# TWE-Lite_USB.net
KiCad netlist of a schematic drawn in EAGLE
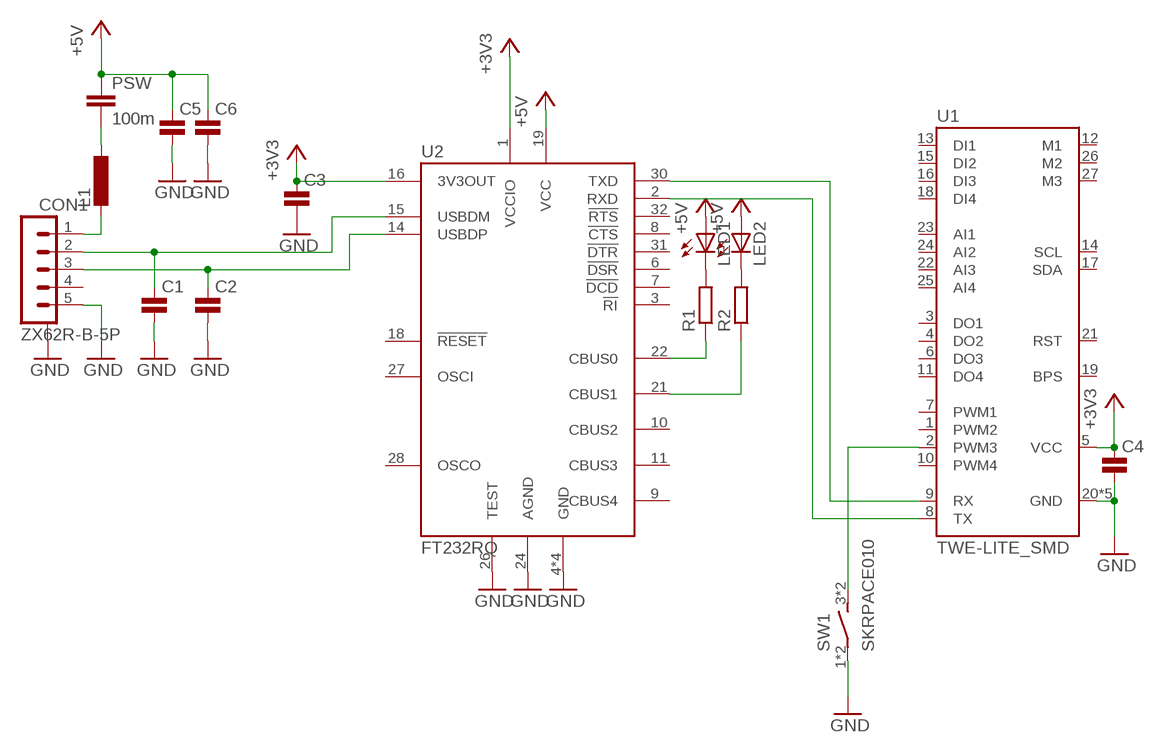
[diagram p0: schematic, sheet 1]

(export (version "E")
  (design (tool "Eeschema 10.0.6"))
  (components
    (comp (ref "C1")
      (value "C0402")
      (footprint "eagle-import:0402")
      (libsource (lib "eagle-import") (part "C0402"))
    )
    (comp (ref "C2")
      (value "C0402")
      (footprint "eagle-import:0402")
      (libsource (lib "eagle-import") (part "C0402"))
    )
    (comp (ref "C3")
      (value "C0402")
      (footprint "eagle-import:0402")
      (libsource (lib "eagle-import") (part "C0402"))
    )
    (comp (ref "C4")
      (value "C0402")
      (footprint "eagle-import:0402")
      (libsource (lib "eagle-import") (part "C0402"))
    )
    (comp (ref "C5")
      (value "C0402")
      (footprint "eagle-import:0402")
      (libsource (lib "eagle-import") (part "C0402"))
    )
    (comp (ref "C6")
      (value "C0402")
      (footprint "eagle-import:0402")
      (libsource (lib "eagle-import") (part "C0402"))
    )
    (comp (ref "CON1")
      (value "ZX62R-B-5P")
      (footprint "eagle-import:MICRO-B")
      (libsource (lib "eagle-import") (part "ZX62R-B-5P"))
    )
    (comp (ref "L1")
      (value "L-EU")
      (footprint "eagle-import:C0603K")
      (libsource (lib "eagle-import") (part "L-EU"))
    )
    (comp (ref "LED1")
      (value "LEDSML0603")
      (footprint "eagle-import:SML0603")
      (libsource (lib "eagle-import") (part "LEDSML0603"))
    )
    (comp (ref "LED2")
      (value "LEDSML0603")
      (footprint "eagle-import:SML0603")
      (libsource (lib "eagle-import") (part "LEDSML0603"))
    )
    (comp (ref "PSW")
      (value "100m")
      (footprint "eagle-import:C3225")
      (libsource (lib "eagle-import") (part "C-EUC3225"))
    )
    (comp (ref "R1")
      (value "R-EU_R0402")
      (footprint "eagle-import:R0402")
      (libsource (lib "eagle-import") (part "R-EU_R0402"))
    )
    (comp (ref "R2")
      (value "R-EU_R0402")
      (footprint "eagle-import:R0402")
      (libsource (lib "eagle-import") (part "R-EU_R0402"))
    )
    (comp (ref "SW1")
      (value "SKRPACE010")
      (footprint "eagle-import:SKRPACE010")
      (libsource (lib "eagle-import") (part "SKRPACE010"))
    )
    (comp (ref "U1")
      (value "TWE-LITE_SMD")
      (footprint "eagle-import:LITE")
      (libsource (lib "eagle-import") (part "TWE-LITE_SMD"))
    )
    (comp (ref "U2")
      (value "FT232RQ")
      (footprint "eagle-import:QFN32")
      (libsource (lib "eagle-import") (part "FT232RQ"))
    )
  )
  (nets
    (net (code "1") (name "+3V3") (class "Default")
      (node (ref "C3") (pin "1") (pinfunction "P$1_1") (pintype "passive"))
      (node (ref "C4") (pin "1") (pinfunction "P$1_1") (pintype "passive"))
      (node (ref "U1") (pin "5") (pinfunction "VCC_5") (pintype "power_in"))
      (node (ref "U2") (pin "1") (pinfunction "VCCIO_1") (pintype "power_in"))
      (node (ref "U2") (pin "16") (pinfunction "3V3OUT_16") (pintype "output"))
    )
    (net (code "2") (name "+5V") (class "Default")
      (node (ref "C5") (pin "1") (pinfunction "P$1_1") (pintype "passive"))
      (node (ref "C6") (pin "1") (pinfunction "P$1_1") (pintype "passive"))
      (node (ref "LED1") (pin "A") (pinfunction "A_A") (pintype "passive"))
      (node (ref "LED2") (pin "A") (pinfunction "A_A") (pintype "passive"))
      (node (ref "PSW") (pin "1") (pinfunction "1_1") (pintype "passive"))
      (node (ref "U2") (pin "19") (pinfunction "VCC_19") (pintype "power_in"))
    )
    (net (code "3") (name "GND") (class "Default")
      (node (ref "C1") (pin "2") (pinfunction "P$2_2") (pintype "passive"))
      (node (ref "C2") (pin "2") (pinfunction "P$2_2") (pintype "passive"))
      (node (ref "C3") (pin "2") (pinfunction "P$2_2") (pintype "passive"))
      (node (ref "C4") (pin "2") (pinfunction "P$2_2") (pintype "passive"))
      (node (ref "C5") (pin "2") (pinfunction "P$2_2") (pintype "passive"))
      (node (ref "C6") (pin "2") (pinfunction "P$2_2") (pintype "passive"))
      (node (ref "CON1") (pin "5") (pinfunction "1.VBUS_5") (pintype "passive"))
      (node (ref "CON1") (pin "CASE@1") (pinfunction "P$1_CASE@1") (pintype "bidirectional"))
      (node (ref "CON1") (pin "CASE@2") (pinfunction "P$1_CASE@2") (pintype "bidirectional"))
      (node (ref "CON1") (pin "CASE@3") (pinfunction "P$1_CASE@3") (pintype "bidirectional"))
      (node (ref "CON1") (pin "CASE@4") (pinfunction "P$1_CASE@4") (pintype "bidirectional"))
      (node (ref "SW1") (pin "1") (pinfunction "P_1") (pintype "passive"))
      (node (ref "SW1") (pin "2") (pinfunction "P_2") (pintype "passive"))
      (node (ref "U1") (pin "20") (pinfunction "GND_20") (pintype "power_in"))
      (node (ref "U1") (pin "28") (pinfunction "GND_28") (pintype "power_in"))
      (node (ref "U1") (pin "30") (pinfunction "GND_30") (pintype "power_in"))
      (node (ref "U1") (pin "31") (pinfunction "GND_31") (pintype "power_in"))
      (node (ref "U1") (pin "32") (pinfunction "GND_32") (pintype "power_in"))
      (node (ref "U2") (pin "17") (pinfunction "GND_17") (pintype "power_in"))
      (node (ref "U2") (pin "20") (pinfunction "GND_20") (pintype "power_in"))
      (node (ref "U2") (pin "24") (pinfunction "AGND_24") (pintype "power_in"))
      (node (ref "U2") (pin "26") (pinfunction "TEST_26") (pintype "input"))
      (node (ref "U2") (pin "4") (pinfunction "GND_4") (pintype "power_in"))
      (node (ref "U2") (pin "PAD") (pinfunction "GND_PAD") (pintype "power_in"))
    )
    (net (code "4") (name "Net-(C1-P$1)") (class "Default")
      (node (ref "C1") (pin "1") (pinfunction "P$1_1") (pintype "passive"))
      (node (ref "CON1") (pin "2") (pinfunction "4.ID_2") (pintype "passive"))
      (node (ref "U2") (pin "15") (pinfunction "USBDM_15") (pintype "bidirectional"))
    )
    (net (code "5") (name "Net-(C2-P$1)") (class "Default")
      (node (ref "C2") (pin "1") (pinfunction "P$1_1") (pintype "passive"))
      (node (ref "CON1") (pin "3") (pinfunction "3.D+_3") (pintype "passive"))
      (node (ref "U2") (pin "14") (pinfunction "USBDP_14") (pintype "bidirectional"))
    )
    (net (code "6") (name "Net-(CON1-5.GND)") (class "Default")
      (node (ref "CON1") (pin "1") (pinfunction "5.GND_1") (pintype "passive"))
      (node (ref "L1") (pin "2") (pinfunction "2_2") (pintype "passive"))
    )
    (net (code "7") (name "Net-(L1-Pad1)") (class "Default")
      (node (ref "L1") (pin "1") (pinfunction "1_1") (pintype "passive"))
      (node (ref "PSW") (pin "2") (pinfunction "2_2") (pintype "passive"))
    )
    (net (code "8") (name "Net-(LED1-PadC)") (class "Default")
      (node (ref "LED1") (pin "C") (pinfunction "C_C") (pintype "passive"))
      (node (ref "R1") (pin "2") (pinfunction "2_2") (pintype "passive"))
    )
    (net (code "9") (name "Net-(LED2-PadC)") (class "Default")
      (node (ref "LED2") (pin "C") (pinfunction "C_C") (pintype "passive"))
      (node (ref "R2") (pin "2") (pinfunction "2_2") (pintype "passive"))
    )
    (net (code "10") (name "Net-(U1-PWM3)") (class "Default")
      (node (ref "SW1") (pin "3") (pinfunction "S_3") (pintype "passive"))
      (node (ref "SW1") (pin "4") (pinfunction "S_4") (pintype "passive"))
      (node (ref "U1") (pin "2") (pinfunction "PWM3_2") (pintype "output"))
    )
    (net (code "11") (name "Net-(U1-RX)") (class "Default")
      (node (ref "U1") (pin "9") (pinfunction "RX_9") (pintype "input"))
      (node (ref "U2") (pin "30") (pinfunction "TXD_30") (pintype "output"))
    )
    (net (code "12") (name "Net-(U1-TX)") (class "Default")
      (node (ref "U1") (pin "8") (pinfunction "TX_8") (pintype "output"))
      (node (ref "U2") (pin "2") (pinfunction "RXD_2") (pintype "input"))
    )
    (net (code "13") (name "Net-(U2-CBUS0)") (class "Default")
      (node (ref "R1") (pin "1") (pinfunction "1_1") (pintype "passive"))
      (node (ref "U2") (pin "22") (pinfunction "CBUS0_22") (pintype "bidirectional"))
    )
    (net (code "14") (name "Net-(U2-CBUS1)") (class "Default")
      (node (ref "R2") (pin "1") (pinfunction "1_1") (pintype "passive"))
      (node (ref "U2") (pin "21") (pinfunction "CBUS1_21") (pintype "bidirectional"))
    )
    (net (code "15") (name "unconnected-(CON1-2.D--Pad4)") (class "Default")
      (node (ref "CON1") (pin "4") (pinfunction "2.D-_4") (pintype "passive"))
    )
    (net (code "16") (name "unconnected-(U1-AI1-Pad23)") (class "Default")
      (node (ref "U1") (pin "23") (pinfunction "AI1_23") (pintype "input"))
    )
    (net (code "17") (name "unconnected-(U1-AI2-Pad24)") (class "Default")
      (node (ref "U1") (pin "24") (pinfunction "AI2_24") (pintype "input"))
    )
    (net (code "18") (name "unconnected-(U1-AI3-Pad22)") (class "Default")
      (node (ref "U1") (pin "22") (pinfunction "AI3_22") (pintype "input"))
    )
    (net (code "19") (name "unconnected-(U1-AI4-Pad25)") (class "Default")
      (node (ref "U1") (pin "25") (pinfunction "AI4_25") (pintype "input"))
    )
    (net (code "20") (name "unconnected-(U1-BPS-Pad19)") (class "Default")
      (node (ref "U1") (pin "19") (pinfunction "BPS_19") (pintype "input"))
    )
    (net (code "21") (name "unconnected-(U1-DI1-Pad13)") (class "Default")
      (node (ref "U1") (pin "13") (pinfunction "DI1_13") (pintype "input"))
    )
    (net (code "22") (name "unconnected-(U1-DI2-Pad15)") (class "Default")
      (node (ref "U1") (pin "15") (pinfunction "DI2_15") (pintype "input"))
    )
    (net (code "23") (name "unconnected-(U1-DI3-Pad16)") (class "Default")
      (node (ref "U1") (pin "16") (pinfunction "DI3_16") (pintype "input"))
    )
    (net (code "24") (name "unconnected-(U1-DI4-Pad18)") (class "Default")
      (node (ref "U1") (pin "18") (pinfunction "DI4_18") (pintype "input"))
    )
    (net (code "25") (name "unconnected-(U1-DO1-Pad3)") (class "Default")
      (node (ref "U1") (pin "3") (pinfunction "DO1_3") (pintype "output"))
    )
    (net (code "26") (name "unconnected-(U1-DO2-Pad4)") (class "Default")
      (node (ref "U1") (pin "4") (pinfunction "DO2_4") (pintype "output"))
    )
    (net (code "27") (name "unconnected-(U1-DO3-Pad6)") (class "Default")
      (node (ref "U1") (pin "6") (pinfunction "DO3_6") (pintype "output"))
    )
    (net (code "28") (name "unconnected-(U1-DO4-Pad11)") (class "Default")
      (node (ref "U1") (pin "11") (pinfunction "DO4_11") (pintype "output"))
    )
    (net (code "29") (name "unconnected-(U1-M1-Pad12)") (class "Default")
      (node (ref "U1") (pin "12") (pinfunction "M1_12") (pintype "input"))
    )
    (net (code "30") (name "unconnected-(U1-M2-Pad26)") (class "Default")
      (node (ref "U1") (pin "26") (pinfunction "M2_26") (pintype "input"))
    )
    (net (code "31") (name "unconnected-(U1-M3-Pad27)") (class "Default")
      (node (ref "U1") (pin "27") (pinfunction "M3_27") (pintype "input"))
    )
    (net (code "32") (name "unconnected-(U1-PWM1-Pad7)") (class "Default")
      (node (ref "U1") (pin "7") (pinfunction "PWM1_7") (pintype "output"))
    )
    (net (code "33") (name "unconnected-(U1-PWM2-Pad1)") (class "Default")
      (node (ref "U1") (pin "1") (pinfunction "PWM2_1") (pintype "output"))
    )
    (net (code "34") (name "unconnected-(U1-PWM4-Pad10)") (class "Default")
      (node (ref "U1") (pin "10") (pinfunction "PWM4_10") (pintype "output"))
    )
    (net (code "35") (name "unconnected-(U1-RST-Pad21)") (class "Default")
      (node (ref "U1") (pin "21") (pinfunction "RST_21") (pintype "input"))
    )
    (net (code "36") (name "unconnected-(U1-SCL-Pad14)") (class "Default")
      (node (ref "U1") (pin "14") (pinfunction "SCL_14") (pintype "bidirectional"))
    )
    (net (code "37") (name "unconnected-(U1-SDA-Pad17)") (class "Default")
      (node (ref "U1") (pin "17") (pinfunction "SDA_17") (pintype "bidirectional"))
    )
    (net (code "38") (name "unconnected-(U2-CBUS2-Pad10)") (class "Default")
      (node (ref "U2") (pin "10") (pinfunction "CBUS2_10") (pintype "bidirectional"))
    )
    (net (code "39") (name "unconnected-(U2-CBUS3-Pad11)") (class "Default")
      (node (ref "U2") (pin "11") (pinfunction "CBUS3_11") (pintype "bidirectional"))
    )
    (net (code "40") (name "unconnected-(U2-CBUS4-Pad9)") (class "Default")
      (node (ref "U2") (pin "9") (pinfunction "CBUS4_9") (pintype "bidirectional"))
    )
    (net (code "41") (name "unconnected-(U2-OSCI-Pad27)") (class "Default")
      (node (ref "U2") (pin "27") (pinfunction "OSCI_27") (pintype "input"))
    )
    (net (code "42") (name "unconnected-(U2-OSCO-Pad28)") (class "Default")
      (node (ref "U2") (pin "28") (pinfunction "OSCO_28") (pintype "output"))
    )
    (net (code "43") (name "unconnected-(U2-~{CTS}-Pad8)") (class "Default")
      (node (ref "U2") (pin "8") (pinfunction "~{CTS}_8") (pintype "input"))
    )
    (net (code "44") (name "unconnected-(U2-~{DCD}-Pad7)") (class "Default")
      (node (ref "U2") (pin "7") (pinfunction "~{DCD}_7") (pintype "input"))
    )
    (net (code "45") (name "unconnected-(U2-~{DSR}-Pad6)") (class "Default")
      (node (ref "U2") (pin "6") (pinfunction "~{DSR}_6") (pintype "input"))
    )
    (net (code "46") (name "unconnected-(U2-~{DTR}-Pad31)") (class "Default")
      (node (ref "U2") (pin "31") (pinfunction "~{DTR}_31") (pintype "output"))
    )
    (net (code "47") (name "unconnected-(U2-~{RESET}-Pad18)") (class "Default")
      (node (ref "U2") (pin "18") (pinfunction "~{RESET}_18") (pintype "input"))
    )
    (net (code "48") (name "unconnected-(U2-~{RI}-Pad3)") (class "Default")
      (node (ref "U2") (pin "3") (pinfunction "~{RI}_3") (pintype "input"))
    )
    (net (code "49") (name "unconnected-(U2-~{RTS}-Pad32)") (class "Default")
      (node (ref "U2") (pin "32") (pinfunction "~{RTS}_32") (pintype "output"))
    )
  )
)
